# Sheet2.net
KiCad netlist of a schematic drawn in Altium Designer
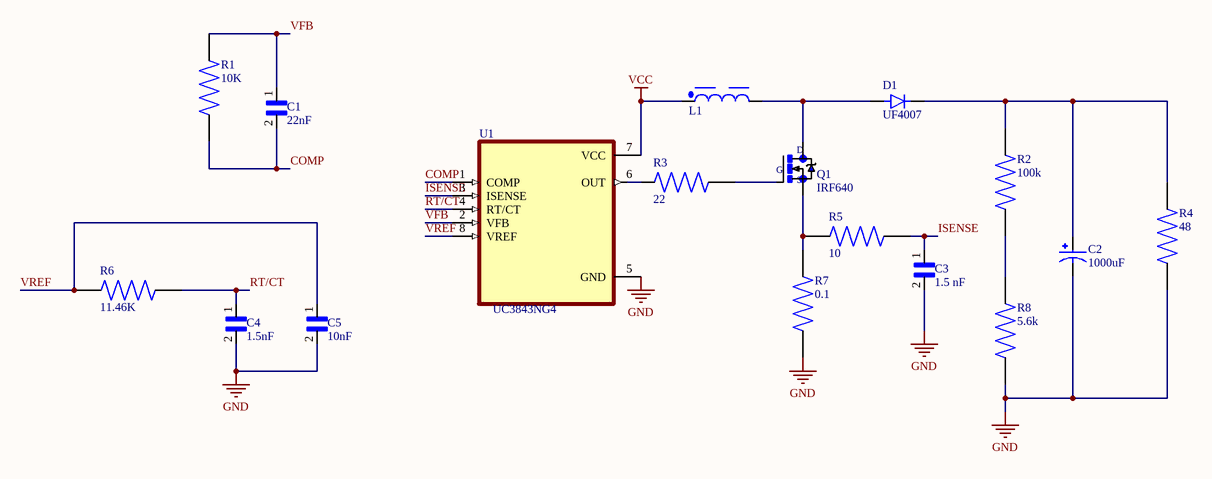
[diagram p0: Sheet2.SchDoc]

(export (version "E")
  (design (tool "Eeschema 10.0.6"))
  (components
    (comp (ref "C1")
      (value "22nF")
      (footprint "CAP_RDER71H223K0M1H03A")
      (description "Cap Ceramic 1pF 50V C0G 0.25pF Radial 5mm 125C Ammo")
      (fields (field (name "MP") "RDER71H223K0M1H03A"))
      (libsource (lib "22nF_RDER71H223K0M1H03A") (part "RDER71H223K0M1H03A"))
    )
    (comp (ref "C2")
      (value "1000uF")
      (footprint "CAPPRD500W60D1000H1600")
      (description "CAP ALUM 1000UF 20% 16V RAD TH")
      (fields (field (name "MF") "Panasonic") (field (name "MP") "EEUFK1C102B"))
      (libsource (lib "1000uF_EEUFK1C102B") (part "EEUFK1C102B"))
    )
    (comp (ref "C3")
      (value "1.5 nF")
      (footprint "CAP TH ALPOLY D8.00mm S3.50mm H21.50mm")
      (description "Lead Capacitor X7R_EIA_ with Capacitance: 10000pF and Rated Voltage: 50Vdc")
      (fields (field (name "MP") "RDER71H103K0K1H03B") (field (name "MF") "Murata"))
      (libsource (lib "10nF_RDER71H103K0K1H03B") (part "RDER71H103K0K1H03B"))
    )
    (comp (ref "C4")
      (value "1.5nF")
      (footprint "CAPRR750W60L1000T450H1000")
      (fields (field (name "MP") "ECQE6152KF"))
      (libsource (lib "1.5nF_ECQE6152KF") (part "ECQE6152KF"))
    )
    (comp (ref "C5")
      (value "10nF")
      (footprint "CAP_RDER71H103K0K1H03B")
      (description "Lead Capacitor X7R_EIA_ with Capacitance: 10000pF and Rated Voltage: 50Vdc")
      (fields (field (name "MP") "RDER71H103K0K1H03B") (field (name "MF") "Murata"))
      (libsource (lib "10nF_RDER71H103K0K1H03B") (part "RDER71H103K0K1H03B"))
    )
    (comp (ref "D1")
      (value "UF4007")
      (footprint "DIOAD1036W78L470D235")
      (description "75ns, 1A, 1000V, High Efficient Recovery Rectifier")
      (fields (field (name "MF") "Taiwan Semiconductor"))
      (libsource (lib "UF4007") (part "UF4007"))
    )
    (comp (ref "L1")
      (value "100uH, 2.45A")
      (footprint "WE-TI_1016")
      (description "WE-TI Radial Leaded Wire Wound Inductor, size 1016, 100uH, 2.45A, 0.1Ohm")
      (fields
        (field (name "MANUFACTURER PART NUMBER") "7447221101")
        (field (name "MANUFACTURER") "Wurth Elektronik")
      )
      (libsource (lib "100uH") (part "7447221101"))
    )
    (comp (ref "Q1")
      (value "IRF640")
      (footprint "*TO220V")
      (description "Single-Gate MOSFET Transistors 200V Single N-Channel HEXFET")
      (fields (field (name "MF") "STMicroelectronics"))
      (libsource (lib "IRF640") (part "IRF640"))
    )
    (comp (ref "R1")
      (value "10K")
      (footprint "RESAD1100W55L680D260")
      (description "1.07 kOhms Â±1% 0.25W, 1/4W Through Hole Resistor Axial - Metal Film")
      (fields (field (name "MF") "Yageo") (field (name "MP") "MFR-25FBF52-1K"))
      (libsource (lib "MFR-25FBF52-1K") (part "MFR-25FBF52-1K"))
    )
    (comp (ref "R2")
      (value "100k")
      (footprint "RESAD1100W55L680D260")
      (description "1.07 kOhms Â±1% 0.25W, 1/4W Through Hole Resistor Axial - Metal Film")
      (fields (field (name "MF") "Yageo") (field (name "MP") "MFR-25FBF52-1K"))
      (libsource (lib "MFR-25FBF52-1K") (part "MFR-25FBF52-1K"))
    )
    (comp (ref "R3")
      (value "22")
      (footprint "RESAD1100W55L680D260")
      (description "1.07 kOhms Â±1% 0.25W, 1/4W Through Hole Resistor Axial - Metal Film")
      (fields (field (name "MF") "Yageo") (field (name "MP") "MFR-25FBF52-1K"))
      (libsource (lib "MFR-25FBF52-1K") (part "MFR-25FBF52-1K"))
    )
    (comp (ref "R4")
      (value "48")
      (footprint "RESAD1100W55L680D260")
      (description "1.07 kOhms Â±1% 0.25W, 1/4W Through Hole Resistor Axial - Metal Film")
      (fields (field (name "MF") "Yageo") (field (name "MP") "MFR-25FBF52-1K"))
      (libsource (lib "MFR-25FBF52-1K") (part "MFR-25FBF52-1K"))
    )
    (comp (ref "R5")
      (value "10")
      (footprint "RESAD1100W55L680D260")
      (description "1.07 kOhms Â±1% 0.25W, 1/4W Through Hole Resistor Axial - Metal Film")
      (fields (field (name "MF") "Yageo") (field (name "MP") "MFR-25FBF52-1K"))
      (libsource (lib "MFR-25FBF52-1K") (part "MFR-25FBF52-1K"))
    )
    (comp (ref "R6")
      (value "11.46K")
      (footprint "RESAD1100W55L680D260")
      (description "1.07 kOhms Â±1% 0.25W, 1/4W Through Hole Resistor Axial - Metal Film")
      (fields (field (name "MF") "Yageo") (field (name "MP") "MFR-25FBF52-1K"))
      (libsource (lib "MFR-25FBF52-1K") (part "MFR-25FBF52-1K"))
    )
    (comp (ref "R7")
      (value "0.1")
      (footprint "RESAD1100W55L680D260")
      (description "1.07 kOhms Â±1% 0.25W, 1/4W Through Hole Resistor Axial - Metal Film")
      (fields (field (name "MF") "Yageo") (field (name "MP") "MFR-25FBF52-1K"))
      (libsource (lib "MFR-25FBF52-1K") (part "MFR-25FBF52-1K"))
    )
    (comp (ref "R8")
      (value "5.6k")
      (footprint "RESAD1100W55L680D260")
      (description "1.07 kOhms Â±1% 0.25W, 1/4W Through Hole Resistor Axial - Metal Film")
      (fields (field (name "MF") "Yageo") (field (name "MP") "MFR-25FBF52-1K"))
      (libsource (lib "MFR-25FBF52-1K") (part "MFR-25FBF52-1K"))
    )
    (comp (ref "U1")
      (value "UC3843NG4")
      (footprint "DIP794W45P254L959H508Q8")
      (fields (field (name "MF") "Texas Instruments"))
      (libsource (lib "UC3843NG4") (part "UC3843NG4"))
    )
  )
  (nets
    (net (code "1") (name "/COMP") (class "Default")
      (node (ref "C1") (pin "2") (pinfunction "2_2") (pintype "passive"))
      (node (ref "R1") (pin "1") (pinfunction "1_1") (pintype "passive"))
      (node (ref "U1") (pin "1") (pinfunction "COMP_1") (pintype "input"))
    )
    (net (code "2") (name "/ISENSE") (class "Default")
      (node (ref "C3") (pin "1") (pinfunction "1_1") (pintype "passive"))
      (node (ref "R5") (pin "1") (pinfunction "1_1") (pintype "passive"))
      (node (ref "U1") (pin "3") (pinfunction "ISENSE_3") (pintype "input"))
    )
    (net (code "3") (name "/RT{slash}CT") (class "Default")
      (node (ref "C4") (pin "1") (pinfunction "1_1") (pintype "passive"))
      (node (ref "R6") (pin "2") (pinfunction "2_2") (pintype "passive"))
      (node (ref "U1") (pin "4") (pinfunction "RT/CT_4") (pintype "input"))
    )
    (net (code "4") (name "/VFB") (class "Default")
      (node (ref "C1") (pin "1") (pinfunction "1_1") (pintype "passive"))
      (node (ref "R1") (pin "2") (pinfunction "2_2") (pintype "passive"))
      (node (ref "U1") (pin "2") (pinfunction "VFB_2") (pintype "input"))
    )
    (net (code "5") (name "/VREF") (class "Default")
      (node (ref "C5") (pin "1") (pinfunction "1_1") (pintype "passive"))
      (node (ref "R6") (pin "1") (pinfunction "1_1") (pintype "passive"))
      (node (ref "U1") (pin "8") (pinfunction "VREF_8") (pintype "input"))
    )
    (net (code "6") (name "GND") (class "Default")
      (node (ref "C2") (pin "N") (pinfunction "N_N") (pintype "passive"))
      (node (ref "C3") (pin "2") (pinfunction "2_2") (pintype "passive"))
      (node (ref "C4") (pin "2") (pinfunction "2_2") (pintype "passive"))
      (node (ref "C5") (pin "2") (pinfunction "2_2") (pintype "passive"))
      (node (ref "R4") (pin "1") (pinfunction "1_1") (pintype "passive"))
      (node (ref "R7") (pin "1") (pinfunction "1_1") (pintype "passive"))
      (node (ref "R8") (pin "1") (pinfunction "1_1") (pintype "passive"))
      (node (ref "U1") (pin "5") (pinfunction "GND_5") (pintype "power_in"))
    )
    (net (code "7") (name "Net-(D1-K)") (class "Default")
      (node (ref "C2") (pin "P") (pinfunction "P_P") (pintype "passive"))
      (node (ref "D1") (pin "C") (pinfunction "K_C") (pintype "passive"))
      (node (ref "R2") (pin "2") (pinfunction "2_2") (pintype "passive"))
      (node (ref "R4") (pin "2") (pinfunction "2_2") (pintype "passive"))
    )
    (net (code "8") (name "Net-(Q1-D)") (class "Default")
      (node (ref "D1") (pin "A") (pinfunction "A_A") (pintype "passive"))
      (node (ref "L1") (pin "2") (pinfunction "2_2") (pintype "passive"))
      (node (ref "Q1") (pin "2") (pinfunction "D_2") (pintype "passive"))
    )
    (net (code "9") (name "Net-(Q1-G)") (class "Default")
      (node (ref "Q1") (pin "1") (pinfunction "G_1") (pintype "passive"))
      (node (ref "R3") (pin "1") (pinfunction "1_1") (pintype "passive"))
    )
    (net (code "10") (name "Net-(Q1-S)") (class "Default")
      (node (ref "Q1") (pin "3") (pinfunction "S_3") (pintype "passive"))
      (node (ref "R5") (pin "2") (pinfunction "2_2") (pintype "passive"))
      (node (ref "R7") (pin "2") (pinfunction "2_2") (pintype "passive"))
    )
    (net (code "11") (name "Net-(R2-Pad1)") (class "Default")
      (node (ref "R2") (pin "1") (pinfunction "1_1") (pintype "passive"))
      (node (ref "R8") (pin "2") (pinfunction "2_2") (pintype "passive"))
    )
    (net (code "12") (name "Net-(U1-OUT)") (class "Default")
      (node (ref "R3") (pin "2") (pinfunction "2_2") (pintype "passive"))
      (node (ref "U1") (pin "6") (pinfunction "OUT_6") (pintype "output"))
    )
    (net (code "13") (name "VCC") (class "Default")
      (node (ref "L1") (pin "1") (pinfunction "1_1") (pintype "passive"))
      (node (ref "U1") (pin "7") (pinfunction "VCC_7") (pintype "power_in"))
    )
  )
)
